# omni-ultra-l2.net
KiCad netlist of a schematic drawn in EAGLE
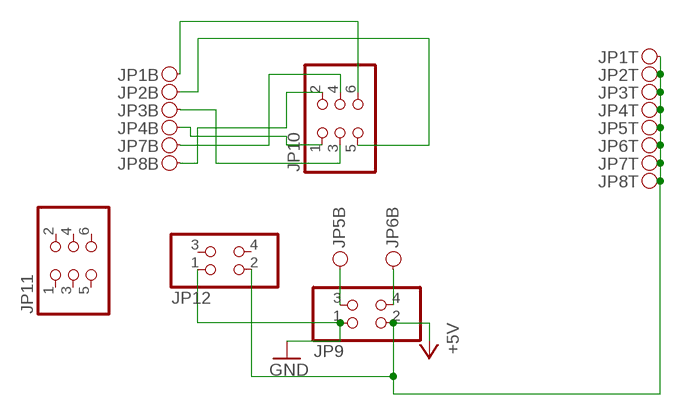
[diagram p0: schematic, sheet 1]

(export (version "E")
  (design (tool "Eeschema 10.0.6"))
  (components
    (comp (ref "JP1")
      (value "PINH2X01")
      (footprint "eagle-import:PINH2X01SMD")
      (libsource (lib "eagle-import") (part "PINH2X01"))
    )
    (comp (ref "JP2")
      (value "PINH2X01")
      (footprint "eagle-import:PINH2X01SMD")
      (libsource (lib "eagle-import") (part "PINH2X01"))
    )
    (comp (ref "JP3")
      (value "PINH2X01")
      (footprint "eagle-import:PINH2X01SMD")
      (libsource (lib "eagle-import") (part "PINH2X01"))
    )
    (comp (ref "JP4")
      (value "PINH2X01")
      (footprint "eagle-import:PINH2X01SMD")
      (libsource (lib "eagle-import") (part "PINH2X01"))
    )
    (comp (ref "JP5")
      (value "PINH2X01")
      (footprint "eagle-import:PINH2X01SMD")
      (libsource (lib "eagle-import") (part "PINH2X01"))
    )
    (comp (ref "JP6")
      (value "PINH2X01")
      (footprint "eagle-import:PINH2X01SMD")
      (libsource (lib "eagle-import") (part "PINH2X01"))
    )
    (comp (ref "JP7")
      (value "PINH2X01")
      (footprint "eagle-import:PINH2X01SMD")
      (libsource (lib "eagle-import") (part "PINH2X01"))
    )
    (comp (ref "JP8")
      (value "PINH2X01")
      (footprint "eagle-import:PINH2X01SMD")
      (libsource (lib "eagle-import") (part "PINH2X01"))
    )
    (comp (ref "JP9")
      (value "PINHD-2X2")
      (footprint "eagle-import:2X02")
      (libsource (lib "eagle-import") (part "PINHD-2X2"))
    )
    (comp (ref "JP10")
      (value "PINHD-2X3")
      (footprint "eagle-import:2X03")
      (libsource (lib "eagle-import") (part "PINHD-2X3"))
    )
    (comp (ref "JP11")
      (value "PINHD-2X3")
      (footprint "eagle-import:2X03")
      (libsource (lib "eagle-import") (part "PINHD-2X3"))
    )
    (comp (ref "JP12")
      (value "PINHD-2X2")
      (footprint "eagle-import:2X02")
      (libsource (lib "eagle-import") (part "PINHD-2X2"))
    )
  )
  (nets
    (net (code "1") (name "+5V") (class "Default")
      (node (ref "JP1") (pin "T1") (pinfunction "1_T1") (pintype "passive"))
      (node (ref "JP12") (pin "2") (pinfunction "2_2") (pintype "passive"))
      (node (ref "JP2") (pin "T1") (pinfunction "1_T1") (pintype "passive"))
      (node (ref "JP3") (pin "T1") (pinfunction "1_T1") (pintype "passive"))
      (node (ref "JP4") (pin "T1") (pinfunction "1_T1") (pintype "passive"))
      (node (ref "JP5") (pin "T1") (pinfunction "1_T1") (pintype "passive"))
      (node (ref "JP6") (pin "T1") (pinfunction "1_T1") (pintype "passive"))
      (node (ref "JP7") (pin "T1") (pinfunction "1_T1") (pintype "passive"))
      (node (ref "JP8") (pin "T1") (pinfunction "1_T1") (pintype "passive"))
      (node (ref "JP9") (pin "2") (pinfunction "2_2") (pintype "passive"))
    )
    (net (code "2") (name "GND") (class "Default")
      (node (ref "JP12") (pin "1") (pinfunction "1_1") (pintype "passive"))
      (node (ref "JP9") (pin "1") (pinfunction "1_1") (pintype "passive"))
    )
    (net (code "3") (name "Net-(JP1A-1)") (class "Default")
      (node (ref "JP1") (pin "B1") (pinfunction "1_B1") (pintype "passive"))
      (node (ref "JP10") (pin "6") (pinfunction "6_6") (pintype "passive"))
    )
    (net (code "4") (name "Net-(JP2A-1)") (class "Default")
      (node (ref "JP10") (pin "5") (pinfunction "5_5") (pintype "passive"))
      (node (ref "JP2") (pin "B1") (pinfunction "1_B1") (pintype "passive"))
    )
    (net (code "5") (name "Net-(JP3A-1)") (class "Default")
      (node (ref "JP10") (pin "3") (pinfunction "3_3") (pintype "passive"))
      (node (ref "JP3") (pin "B1") (pinfunction "1_B1") (pintype "passive"))
    )
    (net (code "6") (name "Net-(JP4A-1)") (class "Default")
      (node (ref "JP10") (pin "1") (pinfunction "1_1") (pintype "passive"))
      (node (ref "JP4") (pin "B1") (pinfunction "1_B1") (pintype "passive"))
    )
    (net (code "7") (name "Net-(JP5A-1)") (class "Default")
      (node (ref "JP5") (pin "B1") (pinfunction "1_B1") (pintype "passive"))
      (node (ref "JP9") (pin "3") (pinfunction "3_3") (pintype "passive"))
    )
    (net (code "8") (name "Net-(JP6A-1)") (class "Default")
      (node (ref "JP6") (pin "B1") (pinfunction "1_B1") (pintype "passive"))
      (node (ref "JP9") (pin "4") (pinfunction "4_4") (pintype "passive"))
    )
    (net (code "9") (name "Net-(JP7A-1)") (class "Default")
      (node (ref "JP10") (pin "4") (pinfunction "4_4") (pintype "passive"))
      (node (ref "JP7") (pin "B1") (pinfunction "1_B1") (pintype "passive"))
    )
    (net (code "10") (name "Net-(JP8A-1)") (class "Default")
      (node (ref "JP10") (pin "2") (pinfunction "2_2") (pintype "passive"))
      (node (ref "JP8") (pin "B1") (pinfunction "1_B1") (pintype "passive"))
    )
    (net (code "11") (name "unconnected-(JP11-Pad1)") (class "Default")
      (node (ref "JP11") (pin "1") (pinfunction "1_1") (pintype "passive"))
    )
    (net (code "12") (name "unconnected-(JP11-Pad2)") (class "Default")
      (node (ref "JP11") (pin "2") (pinfunction "2_2") (pintype "passive"))
    )
    (net (code "13") (name "unconnected-(JP11-Pad3)") (class "Default")
      (node (ref "JP11") (pin "3") (pinfunction "3_3") (pintype "passive"))
    )
    (net (code "14") (name "unconnected-(JP11-Pad4)") (class "Default")
      (node (ref "JP11") (pin "4") (pinfunction "4_4") (pintype "passive"))
    )
    (net (code "15") (name "unconnected-(JP11-Pad5)") (class "Default")
      (node (ref "JP11") (pin "5") (pinfunction "5_5") (pintype "passive"))
    )
    (net (code "16") (name "unconnected-(JP11-Pad6)") (class "Default")
      (node (ref "JP11") (pin "6") (pinfunction "6_6") (pintype "passive"))
    )
    (net (code "17") (name "unconnected-(JP12-Pad3)") (class "Default")
      (node (ref "JP12") (pin "3") (pinfunction "3_3") (pintype "passive"))
    )
    (net (code "18") (name "unconnected-(JP12-Pad4)") (class "Default")
      (node (ref "JP12") (pin "4") (pinfunction "4_4") (pintype "passive"))
    )
  )
)
